# BALISE.net
KiCad netlist of a schematic drawn in EAGLE
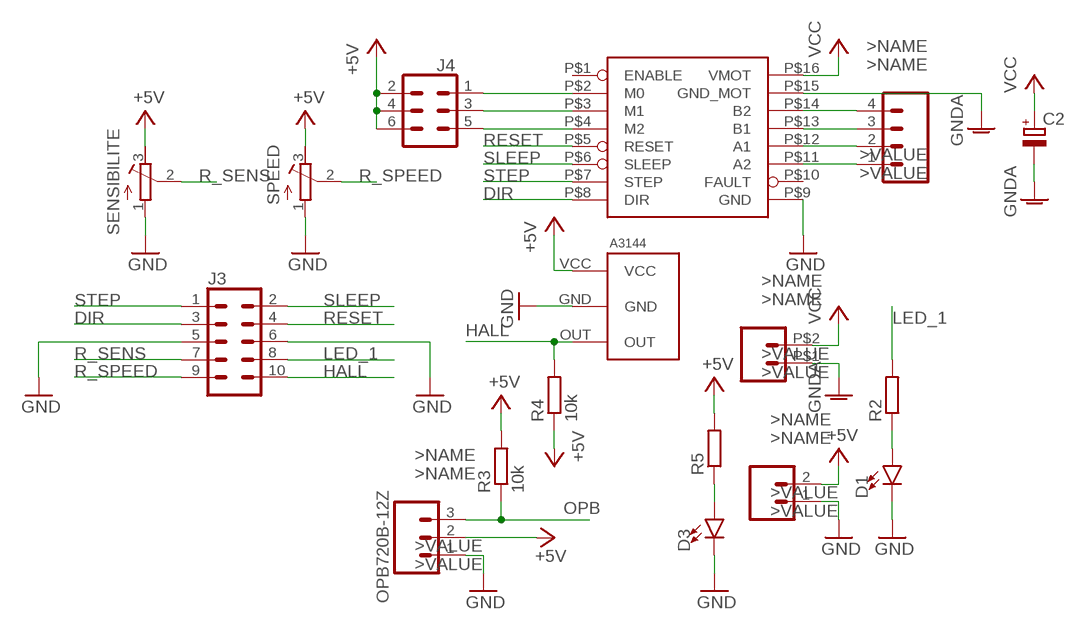
[diagram p0: schematic, sheet 1]

(export (version "E")
  (design (tool "Eeschema 10.0.6"))
  (components
    (comp (ref "A3144")
      (value "A3144_HALL_SENSOR")
      (footprint "eagle-import:A3144_HORIZONTAL")
      (libsource (lib "eagle-import") (part "A3144_HALL_SENSOR"))
    )
    (comp (ref "C2")
      (value "CPOL-EUE3.5-8")
      (footprint "eagle-import:E3,5-8")
      (libsource (lib "eagle-import") (part "CPOL-EUE3.5-8"))
    )
    (comp (ref "D1")
      (value "LED5MM")
      (footprint "eagle-import:LED_5MM")
      (libsource (lib "eagle-import") (part "LED5MM"))
    )
    (comp (ref "D3")
      (value "LED5MM")
      (footprint "eagle-import:LED_5MM")
      (libsource (lib "eagle-import") (part "LED5MM"))
    )
    (comp (ref "J1")
      (value "CONN_04POLAR")
      (footprint "eagle-import:MOLEX-1X4")
      (libsource (lib "eagle-import") (part "CONN_04POLAR"))
    )
    (comp (ref "J2")
      (value "CONN_02POLAR")
      (footprint "eagle-import:MOLEX-1X2")
      (libsource (lib "eagle-import") (part "CONN_02POLAR"))
    )
    (comp (ref "J3")
      (value "CONN_05X2SHD")
      (footprint "eagle-import:2X5-SHROUDED")
      (libsource (lib "eagle-import") (part "CONN_05X2SHD"))
    )
    (comp (ref "J4")
      (value "CONN_03X22X3_SILK_MALE_PTH")
      (footprint "eagle-import:2X3")
      (libsource (lib "eagle-import") (part "CONN_03X22X3_SILK_MALE_PTH"))
    )
    (comp (ref "J5")
      (value "CONN_027A-C")
      (footprint "eagle-import:NSK396-2C")
      (libsource (lib "eagle-import") (part "CONN_027A-C"))
    )
    (comp (ref "OPB720B-12Z")
      (value "CONN_03POLAR")
      (footprint "eagle-import:MOLEX-1X3")
      (libsource (lib "eagle-import") (part "CONN_03POLAR"))
    )
    (comp (ref "R2")
      (value "R-EU_0207/10")
      (footprint "eagle-import:0207_10")
      (libsource (lib "eagle-import") (part "R-EU_0207/10"))
    )
    (comp (ref "R3")
      (value "10k")
      (footprint "eagle-import:0207_10")
      (libsource (lib "eagle-import") (part "R-EU_0207/10"))
    )
    (comp (ref "R4")
      (value "10k")
      (footprint "eagle-import:0207_10")
      (libsource (lib "eagle-import") (part "R-EU_0207/10"))
    )
    (comp (ref "R5")
      (value "R-EU_0207/10")
      (footprint "eagle-import:0207_10")
      (libsource (lib "eagle-import") (part "R-EU_0207/10"))
    )
    (comp (ref "SENSIBILITE")
      (value "R-TRIMM3339P")
      (footprint "eagle-import:RTRIM3339P")
      (libsource (lib "eagle-import") (part "R-TRIMM3339P"))
    )
    (comp (ref "SPEED")
      (value "R-TRIMM3339P")
      (footprint "eagle-import:RTRIM3339P")
      (libsource (lib "eagle-import") (part "R-TRIMM3339P"))
    )
    (comp (ref "U$1")
      (value "DRV8825")
      (footprint "eagle-import:DRIVER_CARRIER_POLOLU_16")
      (libsource (lib "eagle-import") (part "DRV8825"))
    )
  )
  (nets
    (net (code "1") (name "+5V") (class "Default")
      (node (ref "A3144") (pin "VCC") (pinfunction "VCC_VCC") (pintype "power_in"))
      (node (ref "J2") (pin "2") (pinfunction "2_2") (pintype "passive"))
      (node (ref "J4") (pin "2") (pinfunction "2_2") (pintype "bidirectional"))
      (node (ref "J4") (pin "4") (pinfunction "4_4") (pintype "bidirectional"))
      (node (ref "J4") (pin "6") (pinfunction "6_6") (pintype "bidirectional"))
      (node (ref "OPB720B-12Z") (pin "2") (pinfunction "2_2") (pintype "passive"))
      (node (ref "R3") (pin "2") (pinfunction "2_2") (pintype "passive"))
      (node (ref "R4") (pin "1") (pinfunction "1_1") (pintype "passive"))
      (node (ref "R5") (pin "2") (pinfunction "2_2") (pintype "passive"))
      (node (ref "SENSIBILITE") (pin "3") (pinfunction "E_3") (pintype "passive"))
      (node (ref "SPEED") (pin "3") (pinfunction "E_3") (pintype "passive"))
    )
    (net (code "2") (name "/DIR") (class "Default")
      (node (ref "J3") (pin "3") (pinfunction "3_3") (pintype "passive"))
      (node (ref "U$1") (pin "P$8") (pinfunction "DIR_P$8") (pintype "bidirectional"))
    )
    (net (code "3") (name "/HALL") (class "Default")
      (node (ref "A3144") (pin "OUT") (pinfunction "OUT_OUT") (pintype "output"))
      (node (ref "J3") (pin "10") (pinfunction "10_10") (pintype "passive"))
      (node (ref "R4") (pin "2") (pinfunction "2_2") (pintype "passive"))
    )
    (net (code "4") (name "/LED_1") (class "Default")
      (node (ref "J3") (pin "8") (pinfunction "8_8") (pintype "passive"))
      (node (ref "R2") (pin "2") (pinfunction "2_2") (pintype "passive"))
    )
    (net (code "5") (name "/OPB") (class "Default")
      (node (ref "OPB720B-12Z") (pin "3") (pinfunction "3_3") (pintype "passive"))
      (node (ref "R3") (pin "1") (pinfunction "1_1") (pintype "passive"))
    )
    (net (code "6") (name "/RESET") (class "Default")
      (node (ref "J3") (pin "4") (pinfunction "4_4") (pintype "passive"))
      (node (ref "U$1") (pin "P$5") (pinfunction "RESET_P$5") (pintype "bidirectional"))
    )
    (net (code "7") (name "/R_SENS") (class "Default")
      (node (ref "J3") (pin "7") (pinfunction "7_7") (pintype "passive"))
      (node (ref "SENSIBILITE") (pin "2") (pinfunction "S_2") (pintype "passive"))
    )
    (net (code "8") (name "/R_SPEED") (class "Default")
      (node (ref "J3") (pin "9") (pinfunction "9_9") (pintype "passive"))
      (node (ref "SPEED") (pin "2") (pinfunction "S_2") (pintype "passive"))
    )
    (net (code "9") (name "/SLEEP") (class "Default")
      (node (ref "J3") (pin "2") (pinfunction "2_2") (pintype "passive"))
      (node (ref "U$1") (pin "P$6") (pinfunction "SLEEP_P$6") (pintype "bidirectional"))
    )
    (net (code "10") (name "/STEP") (class "Default")
      (node (ref "J3") (pin "1") (pinfunction "1_1") (pintype "passive"))
      (node (ref "U$1") (pin "P$7") (pinfunction "STEP_P$7") (pintype "bidirectional"))
    )
    (net (code "11") (name "GND") (class "Default")
      (node (ref "A3144") (pin "GND") (pinfunction "GND_GND") (pintype "power_in"))
      (node (ref "D1") (pin "K") (pinfunction "C_K") (pintype "passive"))
      (node (ref "D3") (pin "K") (pinfunction "C_K") (pintype "passive"))
      (node (ref "J2") (pin "1") (pinfunction "1_1") (pintype "passive"))
      (node (ref "J3") (pin "5") (pinfunction "5_5") (pintype "passive"))
      (node (ref "J3") (pin "6") (pinfunction "6_6") (pintype "passive"))
      (node (ref "OPB720B-12Z") (pin "1") (pinfunction "1_1") (pintype "passive"))
      (node (ref "SENSIBILITE") (pin "1") (pinfunction "A_1") (pintype "passive"))
      (node (ref "SPEED") (pin "1") (pinfunction "A_1") (pintype "passive"))
      (node (ref "U$1") (pin "P$9") (pinfunction "GND_P$9") (pintype "bidirectional"))
    )
    (net (code "12") (name "GNDA") (class "Default")
      (node (ref "C2") (pin "-") (pinfunction "-_-") (pintype "passive"))
      (node (ref "J5") (pin "P$1") (pinfunction "1_P$1") (pintype "passive"))
      (node (ref "U$1") (pin "P$15") (pinfunction "GND_MOT_P$15") (pintype "bidirectional"))
    )
    (net (code "13") (name "Net-(D1-PadA)") (class "Default")
      (node (ref "D1") (pin "A") (pinfunction "A_A") (pintype "passive"))
      (node (ref "R2") (pin "1") (pinfunction "1_1") (pintype "passive"))
    )
    (net (code "14") (name "Net-(D3-PadA)") (class "Default")
      (node (ref "D3") (pin "A") (pinfunction "A_A") (pintype "passive"))
      (node (ref "R5") (pin "1") (pinfunction "1_1") (pintype "passive"))
    )
    (net (code "15") (name "Net-(U$1-A1)") (class "Default")
      (node (ref "J1") (pin "2") (pinfunction "2_2") (pintype "passive"))
      (node (ref "U$1") (pin "P$12") (pinfunction "A1_P$12") (pintype "bidirectional"))
    )
    (net (code "16") (name "Net-(U$1-A2)") (class "Default")
      (node (ref "J1") (pin "1") (pinfunction "1_1") (pintype "passive"))
      (node (ref "U$1") (pin "P$11") (pinfunction "A2_P$11") (pintype "bidirectional"))
    )
    (net (code "17") (name "Net-(U$1-B1)") (class "Default")
      (node (ref "J1") (pin "3") (pinfunction "3_3") (pintype "passive"))
      (node (ref "U$1") (pin "P$13") (pinfunction "B1_P$13") (pintype "bidirectional"))
    )
    (net (code "18") (name "Net-(U$1-B2)") (class "Default")
      (node (ref "J1") (pin "4") (pinfunction "4_4") (pintype "passive"))
      (node (ref "U$1") (pin "P$14") (pinfunction "B2_P$14") (pintype "bidirectional"))
    )
    (net (code "19") (name "Net-(U$1-M0)") (class "Default")
      (node (ref "J4") (pin "1") (pinfunction "1_1") (pintype "bidirectional"))
      (node (ref "U$1") (pin "P$2") (pinfunction "M0_P$2") (pintype "bidirectional"))
    )
    (net (code "20") (name "Net-(U$1-M1)") (class "Default")
      (node (ref "J4") (pin "3") (pinfunction "3_3") (pintype "bidirectional"))
      (node (ref "U$1") (pin "P$3") (pinfunction "M1_P$3") (pintype "bidirectional"))
    )
    (net (code "21") (name "Net-(U$1-M2)") (class "Default")
      (node (ref "J4") (pin "5") (pinfunction "5_5") (pintype "bidirectional"))
      (node (ref "U$1") (pin "P$4") (pinfunction "M2_P$4") (pintype "bidirectional"))
    )
    (net (code "22") (name "VCC") (class "Default")
      (node (ref "C2") (pin "+") (pinfunction "+_+") (pintype "passive"))
      (node (ref "J5") (pin "P$2") (pinfunction "2_P$2") (pintype "passive"))
      (node (ref "U$1") (pin "P$16") (pinfunction "VMOT_P$16") (pintype "bidirectional"))
    )
    (net (code "23") (name "unconnected-(U$1-ENABLE-PadP$1)") (class "Default")
      (node (ref "U$1") (pin "P$1") (pinfunction "ENABLE_P$1") (pintype "bidirectional"))
    )
    (net (code "24") (name "unconnected-(U$1-FAULT-PadP$10)") (class "Default")
      (node (ref "U$1") (pin "P$10") (pinfunction "FAULT_P$10") (pintype "bidirectional"))
    )
  )
)
